# Sheet1.net
KiCad netlist of a schematic drawn in Altium Designer
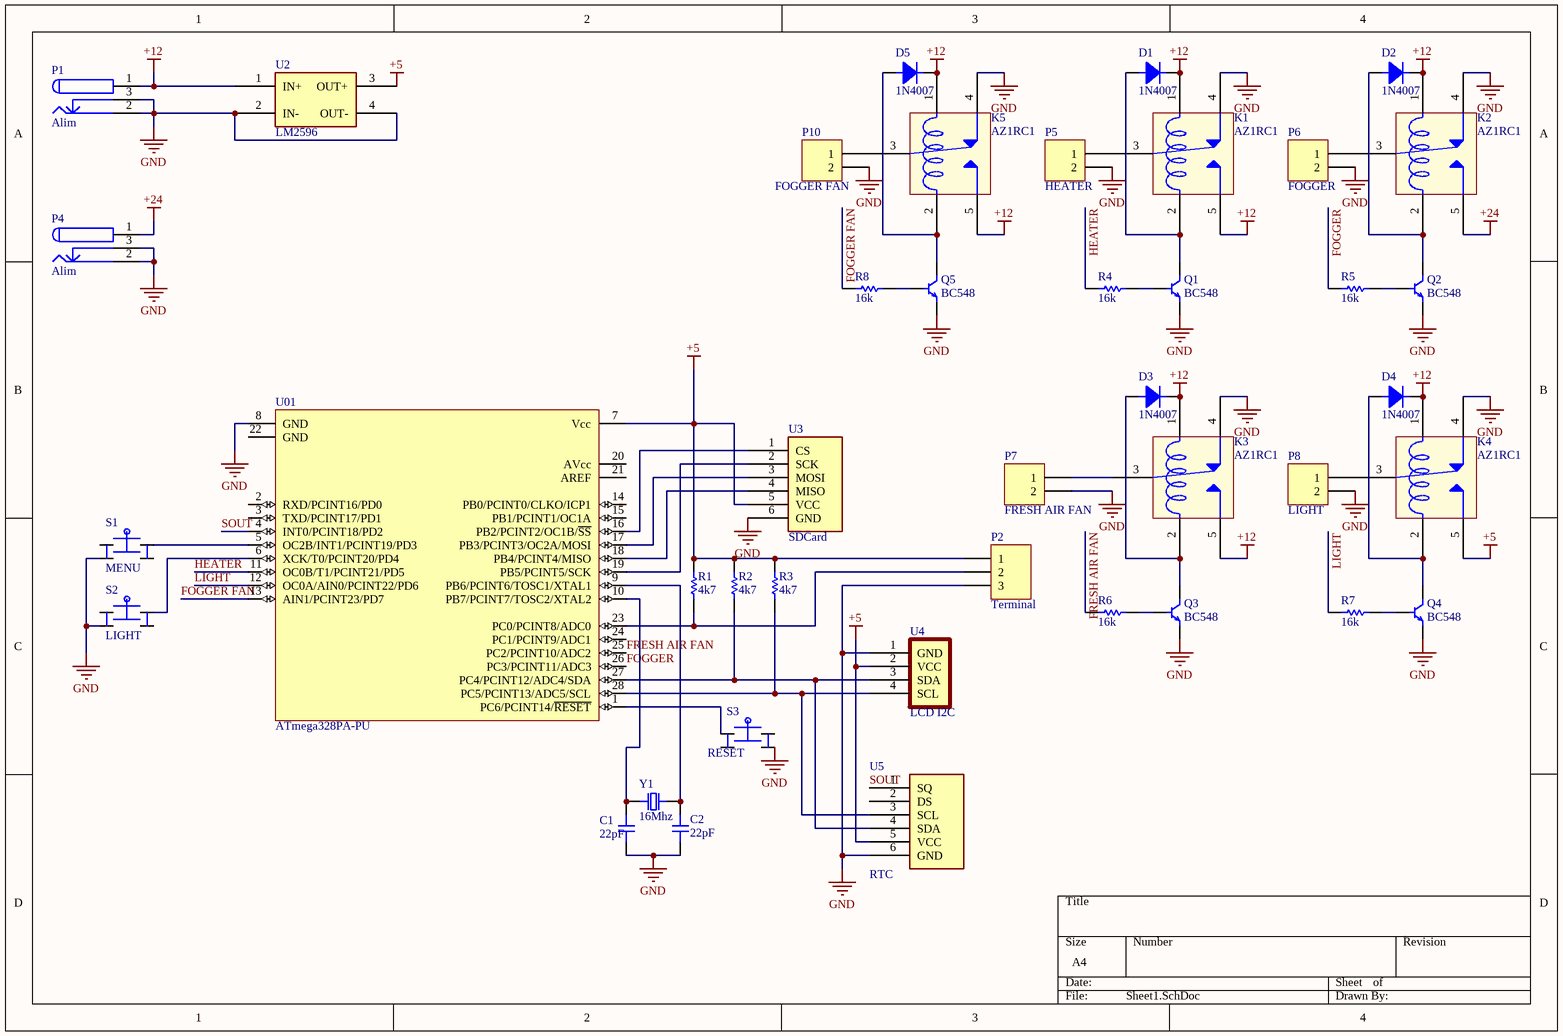
[diagram p0: Sheet1.SchDoc]

(export (version "E")
  (design (tool "Eeschema 10.0.6"))
  (components
    (comp (ref "C1")
      (value "22pF")
      (footprint "C100-200-100")
      (description "Capacitor")
      (fields (field (name "VOLTAGE") "100 V") (field (name "PUBLISHER") "Altium Limited"))
      (libsource (lib "GPDSE") (part "Capacitor"))
    )
    (comp (ref "C2")
      (value "22pF")
      (footprint "C100-200-100")
      (description "Capacitor")
      (fields (field (name "VOLTAGE") "100 V") (field (name "PUBLISHER") "Altium Limited"))
      (libsource (lib "GPDSE") (part "Capacitor"))
    )
    (comp (ref "D1")
      (value "1N4007")
      (footprint "DO-41-Plastic")
      (description "General Purpose Rectifier")
      (libsource (lib "GPDSE") (part "1N4007"))
    )
    (comp (ref "D2")
      (value "1N4007")
      (footprint "DO-41-Plastic")
      (description "General Purpose Rectifier")
      (libsource (lib "GPDSE") (part "1N4007"))
    )
    (comp (ref "D3")
      (value "1N4007")
      (footprint "DO-41-Plastic")
      (description "General Purpose Rectifier")
      (libsource (lib "GPDSE") (part "1N4007"))
    )
    (comp (ref "D4")
      (value "1N4007")
      (footprint "DO-41-Plastic")
      (description "General Purpose Rectifier")
      (libsource (lib "GPDSE") (part "1N4007"))
    )
    (comp (ref "D5")
      (value "1N4007")
      (footprint "DO-41-Plastic")
      (description "General Purpose Rectifier")
      (libsource (lib "GPDSE") (part "1N4007"))
    )
    (comp (ref "K1")
      (value "AZ1RC1")
      (footprint "Relay-A")
      (description "Miniature Relay, 10 A, 6 Vdc, 250 Vac")
      (libsource (lib "GPDSE") (part "AZ1RC1"))
    )
    (comp (ref "K2")
      (value "AZ1RC1")
      (footprint "Relay-A")
      (description "Miniature Relay, 10 A, 6 Vdc, 250 Vac")
      (libsource (lib "GPDSE") (part "AZ1RC1"))
    )
    (comp (ref "K3")
      (value "AZ1RC1")
      (footprint "Relay-A")
      (description "Miniature Relay, 10 A, 6 Vdc, 250 Vac")
      (libsource (lib "GPDSE") (part "AZ1RC1"))
    )
    (comp (ref "K4")
      (value "AZ1RC1")
      (footprint "Relay-A")
      (description "Miniature Relay, 10 A, 6 Vdc, 250 Vac")
      (libsource (lib "GPDSE") (part "AZ1RC1"))
    )
    (comp (ref "K5")
      (value "AZ1RC1")
      (footprint "Relay-A")
      (description "Miniature Relay, 10 A, 6 Vdc, 250 Vac")
      (libsource (lib "GPDSE") (part "AZ1RC1"))
    )
    (comp (ref "P1")
      (value "Alim")
      (footprint "J4-DC-005")
      (description "Jack J4")
      (libsource (lib "GPDSE") (part "Jack_J4"))
    )
    (comp (ref "P2")
      (value "Terminal")
      (footprint "KRE_3")
      (description "Terminal Block 1x3")
      (libsource (lib "GPDSE") (part "KRE_3"))
    )
    (comp (ref "P4")
      (value "Alim")
      (footprint "J4-DC-005")
      (description "Jack J4")
      (libsource (lib "GPDSE") (part "Jack_J4"))
    )
    (comp (ref "P5")
      (value "HEATER")
      (footprint "KRE_2")
      (description "Terminal Block 1x2")
      (libsource (lib "GPDSE") (part "KRE_2"))
    )
    (comp (ref "P6")
      (value "FOGGER")
      (footprint "KRE_2")
      (description "Terminal Block 1x2")
      (libsource (lib "GPDSE") (part "KRE_2"))
    )
    (comp (ref "P7")
      (value "FRESH AIR FAN")
      (footprint "KRE_2")
      (description "Terminal Block 1x2")
      (libsource (lib "GPDSE") (part "KRE_2"))
    )
    (comp (ref "P8")
      (value "LIGHT")
      (footprint "KRE_2")
      (description "Terminal Block 1x2")
      (libsource (lib "GPDSE") (part "KRE_2"))
    )
    (comp (ref "P10")
      (value "FOGGER FAN")
      (footprint "KRE_2")
      (description "Terminal Block 1x2")
      (libsource (lib "GPDSE") (part "KRE_2"))
    )
    (comp (ref "Q1")
      (value "BC548")
      (footprint "TO-92/CBE")
      (description "NPN Epitaxial Silicon Transistor")
      (fields (field (name "COMPLEMENTARY PART") "BC558"))
      (libsource (lib "GPDSE") (part "BC548"))
    )
    (comp (ref "Q2")
      (value "BC548")
      (footprint "TO-92/CBE")
      (description "NPN Epitaxial Silicon Transistor")
      (fields (field (name "COMPLEMENTARY PART") "BC558"))
      (libsource (lib "GPDSE") (part "BC548"))
    )
    (comp (ref "Q3")
      (value "BC548")
      (footprint "TO-92/CBE")
      (description "NPN Epitaxial Silicon Transistor")
      (fields (field (name "COMPLEMENTARY PART") "BC558"))
      (libsource (lib "GPDSE") (part "BC548"))
    )
    (comp (ref "Q4")
      (value "BC548")
      (footprint "TO-92/CBE")
      (description "NPN Epitaxial Silicon Transistor")
      (fields (field (name "COMPLEMENTARY PART") "BC558"))
      (libsource (lib "GPDSE") (part "BC548"))
    )
    (comp (ref "Q5")
      (value "BC548")
      (footprint "TO-92/CBE")
      (description "NPN Epitaxial Silicon Transistor")
      (fields (field (name "COMPLEMENTARY PART") "BC558"))
      (libsource (lib "GPDSE") (part "BC548"))
    )
    (comp (ref "R1")
      (value "4k7")
      (footprint "R400-2.0mm")
      (description "Resistor")
      (fields
        (field (name "TOLERANCE") "5%")
        (field (name "POWER") "1/4 W")
        (field (name "PUBLISHER") "Altium Limited")
      )
      (libsource (lib "GPDSE") (part "Resistor"))
    )
    (comp (ref "R2")
      (value "4k7")
      (footprint "R400-2.0mm")
      (description "Resistor")
      (fields
        (field (name "TOLERANCE") "5%")
        (field (name "POWER") "1/4 W")
        (field (name "PUBLISHER") "Altium Limited")
      )
      (libsource (lib "GPDSE") (part "Resistor"))
    )
    (comp (ref "R3")
      (value "4k7")
      (footprint "R400-2.0mm")
      (description "Resistor")
      (fields
        (field (name "TOLERANCE") "5%")
        (field (name "POWER") "1/4 W")
        (field (name "PUBLISHER") "Altium Limited")
      )
      (libsource (lib "GPDSE") (part "Resistor"))
    )
    (comp (ref "R4")
      (value "16k")
      (footprint "R400-2.0mm")
      (description "Resistor")
      (fields
        (field (name "TOLERANCE") "5%")
        (field (name "POWER") "1/4 W")
        (field (name "PUBLISHER") "Altium Limited")
      )
      (libsource (lib "GPDSE") (part "Resistor"))
    )
    (comp (ref "R5")
      (value "16k")
      (footprint "R400-2.0mm")
      (description "Resistor")
      (fields
        (field (name "TOLERANCE") "5%")
        (field (name "POWER") "1/4 W")
        (field (name "PUBLISHER") "Altium Limited")
      )
      (libsource (lib "GPDSE") (part "Resistor"))
    )
    (comp (ref "R6")
      (value "16k")
      (footprint "R400-2.0mm")
      (description "Resistor")
      (fields
        (field (name "TOLERANCE") "5%")
        (field (name "POWER") "1/4 W")
        (field (name "PUBLISHER") "Altium Limited")
      )
      (libsource (lib "GPDSE") (part "Resistor"))
    )
    (comp (ref "R7")
      (value "16k")
      (footprint "R400-2.0mm")
      (description "Resistor")
      (fields
        (field (name "TOLERANCE") "5%")
        (field (name "POWER") "1/4 W")
        (field (name "PUBLISHER") "Altium Limited")
      )
      (libsource (lib "GPDSE") (part "Resistor"))
    )
    (comp (ref "R8")
      (value "16k")
      (footprint "R400-2.0mm")
      (description "Resistor")
      (fields
        (field (name "TOLERANCE") "5%")
        (field (name "POWER") "1/4 W")
        (field (name "PUBLISHER") "Altium Limited")
      )
      (libsource (lib "GPDSE") (part "Resistor"))
    )
    (comp (ref "S1")
      (value "MENU")
      (footprint "DTS-6.0mm-6.0mm-THT")
      (description "Tactile Switch SPST 4 pins")
      (libsource (lib "GPDSE") (part "PushButton_4"))
    )
    (comp (ref "S2")
      (value "LIGHT")
      (footprint "DTS-6.0mm-6.0mm-THT")
      (description "Tactile Switch SPST 4 pins")
      (libsource (lib "GPDSE") (part "PushButton_4"))
    )
    (comp (ref "S3")
      (value "RESET")
      (footprint "DTS-6.0mm-6.0mm-THT")
      (description "Tactile Switch SPST 4 pins")
      (libsource (lib "GPDSE") (part "PushButton_4"))
    )
    (comp (ref "U01")
      (value "ATmega328PA-PU")
      (footprint "DIP28-300(100)")
      (description "8-bit AVR Microcontroller with 32 KB In-System Programmable Flash")
      (libsource (lib "GPDSE") (part "ATmega328PA-PU"))
    )
    (comp (ref "U2") (value "LM2596") (footprint "LM2596") (libsource (lib "Schlib1") (part "LM2596")))
    (comp (ref "U3") (value "SDCard") (footprint "SDCard") (libsource (lib "Schlib1") (part "SDCard")))
    (comp (ref "U4") (value "LCD I2C") (footprint "LCD_I2C") (libsource (lib "Schlib1") (part "LCD_I2C")))
    (comp (ref "U5") (value "RTC") (footprint "RTC") (libsource (lib "Schlib1") (part "RTC")))
    (comp (ref "Y1")
      (value "16Mhz")
      (footprint "HC49-US-THT")
      (description "Crystal")
      (libsource (lib "GPDSE") (part "Crystal"))
    )
  )
  (nets
    (net (code "1") (name "+5") (class "Default")
      (node (ref "K4") (pin "5") (pinfunction "5_5") (pintype "passive"))
      (node (ref "P2") (pin "1") (pinfunction "1_1") (pintype "passive"))
      (node (ref "R1") (pin "2") (pinfunction "2_2") (pintype "passive"))
      (node (ref "R2") (pin "2") (pinfunction "2_2") (pintype "passive"))
      (node (ref "R3") (pin "2") (pinfunction "2_2") (pintype "passive"))
      (node (ref "U01") (pin "7") (pinfunction "Vcc_7") (pintype "passive"))
      (node (ref "U2") (pin "3") (pinfunction "OUT+_3") (pintype "passive"))
      (node (ref "U3") (pin "5") (pinfunction "VCC_5") (pintype "passive"))
      (node (ref "U4") (pin "2") (pinfunction "VCC_2") (pintype "passive"))
      (node (ref "U5") (pin "5") (pinfunction "VCC_5") (pintype "passive"))
    )
    (net (code "2") (name "+12") (class "Default")
      (node (ref "D1") (pin "K") (pinfunction "K_K") (pintype "passive"))
      (node (ref "D2") (pin "K") (pinfunction "K_K") (pintype "passive"))
      (node (ref "D3") (pin "K") (pinfunction "K_K") (pintype "passive"))
      (node (ref "D4") (pin "K") (pinfunction "K_K") (pintype "passive"))
      (node (ref "D5") (pin "K") (pinfunction "K_K") (pintype "passive"))
      (node (ref "K1") (pin "1") (pinfunction "1_1") (pintype "passive"))
      (node (ref "K1") (pin "5") (pinfunction "5_5") (pintype "passive"))
      (node (ref "K2") (pin "1") (pinfunction "1_1") (pintype "passive"))
      (node (ref "K3") (pin "1") (pinfunction "1_1") (pintype "passive"))
      (node (ref "K3") (pin "5") (pinfunction "5_5") (pintype "passive"))
      (node (ref "K4") (pin "1") (pinfunction "1_1") (pintype "passive"))
      (node (ref "K5") (pin "1") (pinfunction "1_1") (pintype "passive"))
      (node (ref "K5") (pin "5") (pinfunction "5_5") (pintype "passive"))
      (node (ref "P1") (pin "1") (pinfunction "1_1") (pintype "passive"))
      (node (ref "U2") (pin "1") (pinfunction "IN+_1") (pintype "passive"))
    )
    (net (code "3") (name "+24") (class "Default")
      (node (ref "K2") (pin "5") (pinfunction "5_5") (pintype "passive"))
      (node (ref "P4") (pin "1") (pinfunction "1_1") (pintype "passive"))
    )
    (net (code "4") (name "/FOGGER") (class "Default")
      (node (ref "R5") (pin "1") (pinfunction "1_1") (pintype "passive"))
      (node (ref "U01") (pin "26") (pinfunction "PC3/PCINT11/ADC3_26") (pintype "bidirectional"))
    )
    (net (code "5") (name "/FOGGER FAN") (class "Default")
      (node (ref "R8") (pin "1") (pinfunction "1_1") (pintype "passive"))
      (node (ref "U01") (pin "13") (pinfunction "AIN1/PCINT23/PD7_13") (pintype "bidirectional"))
    )
    (net (code "6") (name "/FRESH AIR FAN") (class "Default")
      (node (ref "R6") (pin "1") (pinfunction "1_1") (pintype "passive"))
      (node (ref "U01") (pin "25") (pinfunction "PC2/PCINT10/ADC2_25") (pintype "bidirectional"))
    )
    (net (code "7") (name "/HEATER") (class "Default")
      (node (ref "R4") (pin "1") (pinfunction "1_1") (pintype "passive"))
      (node (ref "U01") (pin "11") (pinfunction "OC0B/T1/PCINT21/PD5_11") (pintype "bidirectional"))
    )
    (net (code "8") (name "/LIGHT") (class "Default")
      (node (ref "R7") (pin "1") (pinfunction "1_1") (pintype "passive"))
      (node (ref "U01") (pin "12") (pinfunction "OC0A/AIN0/PCINT22/PD6_12") (pintype "bidirectional"))
    )
    (net (code "9") (name "/SOUT") (class "Default")
      (node (ref "U01") (pin "4") (pinfunction "INT0/PCINT18/PD2_4") (pintype "bidirectional"))
      (node (ref "U5") (pin "1") (pinfunction "SQ_1") (pintype "passive"))
    )
    (net (code "10") (name "GND") (class "Default")
      (node (ref "C1") (pin "1") (pinfunction "1_1") (pintype "passive"))
      (node (ref "C2") (pin "1") (pinfunction "1_1") (pintype "passive"))
      (node (ref "K1") (pin "4") (pinfunction "4_4") (pintype "passive"))
      (node (ref "K2") (pin "4") (pinfunction "4_4") (pintype "passive"))
      (node (ref "K3") (pin "4") (pinfunction "4_4") (pintype "passive"))
      (node (ref "K4") (pin "4") (pinfunction "4_4") (pintype "passive"))
      (node (ref "K5") (pin "4") (pinfunction "4_4") (pintype "passive"))
      (node (ref "P1") (pin "2") (pinfunction "2_2") (pintype "passive"))
      (node (ref "P1") (pin "3") (pinfunction "3_3") (pintype "passive"))
      (node (ref "P10") (pin "2") (pinfunction "2_2") (pintype "passive"))
      (node (ref "P2") (pin "3") (pinfunction "3_3") (pintype "passive"))
      (node (ref "P4") (pin "2") (pinfunction "2_2") (pintype "passive"))
      (node (ref "P4") (pin "3") (pinfunction "3_3") (pintype "passive"))
      (node (ref "P5") (pin "2") (pinfunction "2_2") (pintype "passive"))
      (node (ref "P6") (pin "2") (pinfunction "2_2") (pintype "passive"))
      (node (ref "P7") (pin "2") (pinfunction "2_2") (pintype "passive"))
      (node (ref "P8") (pin "2") (pinfunction "2_2") (pintype "passive"))
      (node (ref "Q1") (pin "E") (pinfunction "E_E") (pintype "passive"))
      (node (ref "Q2") (pin "E") (pinfunction "E_E") (pintype "passive"))
      (node (ref "Q3") (pin "E") (pinfunction "E_E") (pintype "passive"))
      (node (ref "Q4") (pin "E") (pinfunction "E_E") (pintype "passive"))
      (node (ref "Q5") (pin "E") (pinfunction "E_E") (pintype "passive"))
      (node (ref "S1") (pin "2") (pinfunction "2_2") (pintype "passive"))
      (node (ref "S2") (pin "2") (pinfunction "2_2") (pintype "passive"))
      (node (ref "S3") (pin "4") (pinfunction "4_4") (pintype "passive"))
      (node (ref "U01") (pin "8") (pinfunction "GND_8") (pintype "passive"))
      (node (ref "U2") (pin "2") (pinfunction "IN-_2") (pintype "passive"))
      (node (ref "U2") (pin "4") (pinfunction "OUT-_4") (pintype "passive"))
      (node (ref "U3") (pin "6") (pinfunction "GND_6") (pintype "passive"))
      (node (ref "U4") (pin "1") (pinfunction "GND_1") (pintype "passive"))
      (node (ref "U5") (pin "6") (pinfunction "GND_6") (pintype "passive"))
    )
    (net (code "11") (name "Net-(D1-PadA)") (class "Default")
      (node (ref "D1") (pin "A") (pinfunction "A_A") (pintype "passive"))
      (node (ref "K1") (pin "2") (pinfunction "2_2") (pintype "passive"))
      (node (ref "Q1") (pin "C") (pinfunction "C_C") (pintype "passive"))
    )
    (net (code "12") (name "Net-(D2-PadA)") (class "Default")
      (node (ref "D2") (pin "A") (pinfunction "A_A") (pintype "passive"))
      (node (ref "K2") (pin "2") (pinfunction "2_2") (pintype "passive"))
      (node (ref "Q2") (pin "C") (pinfunction "C_C") (pintype "passive"))
    )
    (net (code "13") (name "Net-(D3-PadA)") (class "Default")
      (node (ref "D3") (pin "A") (pinfunction "A_A") (pintype "passive"))
      (node (ref "K3") (pin "2") (pinfunction "2_2") (pintype "passive"))
      (node (ref "Q3") (pin "C") (pinfunction "C_C") (pintype "passive"))
    )
    (net (code "14") (name "Net-(D4-PadA)") (class "Default")
      (node (ref "D4") (pin "A") (pinfunction "A_A") (pintype "passive"))
      (node (ref "K4") (pin "2") (pinfunction "2_2") (pintype "passive"))
      (node (ref "Q4") (pin "C") (pinfunction "C_C") (pintype "passive"))
    )
    (net (code "15") (name "Net-(D5-PadA)") (class "Default")
      (node (ref "D5") (pin "A") (pinfunction "A_A") (pintype "passive"))
      (node (ref "K5") (pin "2") (pinfunction "2_2") (pintype "passive"))
      (node (ref "Q5") (pin "C") (pinfunction "C_C") (pintype "passive"))
    )
    (net (code "16") (name "Net-(K1-Pad3)") (class "Default")
      (node (ref "K1") (pin "3") (pinfunction "3_3") (pintype "passive"))
      (node (ref "P5") (pin "1") (pinfunction "1_1") (pintype "passive"))
    )
    (net (code "17") (name "Net-(K2-Pad3)") (class "Default")
      (node (ref "K2") (pin "3") (pinfunction "3_3") (pintype "passive"))
      (node (ref "P6") (pin "1") (pinfunction "1_1") (pintype "passive"))
    )
    (net (code "18") (name "Net-(K3-Pad3)") (class "Default")
      (node (ref "K3") (pin "3") (pinfunction "3_3") (pintype "passive"))
      (node (ref "P7") (pin "1") (pinfunction "1_1") (pintype "passive"))
    )
    (net (code "19") (name "Net-(K4-Pad3)") (class "Default")
      (node (ref "K4") (pin "3") (pinfunction "3_3") (pintype "passive"))
      (node (ref "P8") (pin "1") (pinfunction "1_1") (pintype "passive"))
    )
    (net (code "20") (name "Net-(K5-Pad3)") (class "Default")
      (node (ref "K5") (pin "3") (pinfunction "3_3") (pintype "passive"))
      (node (ref "P10") (pin "1") (pinfunction "1_1") (pintype "passive"))
    )
    (net (code "21") (name "Net-(Q1-PadB)") (class "Default")
      (node (ref "Q1") (pin "B") (pinfunction "B_B") (pintype "passive"))
      (node (ref "R4") (pin "2") (pinfunction "2_2") (pintype "passive"))
    )
    (net (code "22") (name "Net-(Q2-PadB)") (class "Default")
      (node (ref "Q2") (pin "B") (pinfunction "B_B") (pintype "passive"))
      (node (ref "R5") (pin "2") (pinfunction "2_2") (pintype "passive"))
    )
    (net (code "23") (name "Net-(Q3-PadB)") (class "Default")
      (node (ref "Q3") (pin "B") (pinfunction "B_B") (pintype "passive"))
      (node (ref "R6") (pin "2") (pinfunction "2_2") (pintype "passive"))
    )
    (net (code "24") (name "Net-(Q4-PadB)") (class "Default")
      (node (ref "Q4") (pin "B") (pinfunction "B_B") (pintype "passive"))
      (node (ref "R7") (pin "2") (pinfunction "2_2") (pintype "passive"))
    )
    (net (code "25") (name "Net-(Q5-PadB)") (class "Default")
      (node (ref "Q5") (pin "B") (pinfunction "B_B") (pintype "passive"))
      (node (ref "R8") (pin "2") (pinfunction "2_2") (pintype "passive"))
    )
    (net (code "26") (name "Net-(U01-OC2B{slash}INT1{slash}PCINT19{slash}PD3)") (class "Default")
      (node (ref "S1") (pin "3") (pinfunction "3_3") (pintype "passive"))
      (node (ref "U01") (pin "5") (pinfunction "OC2B/INT1/PCINT19/PD3_5") (pintype "bidirectional"))
    )
    (net (code "27") (name "Net-(U01-PB2{slash}PCINT2{slash}OC1B{slash}~{SS})") (class "Default")
      (node (ref "U01") (pin "16") (pinfunction "PB2/PCINT2/OC1B/~{SS}_16") (pintype "bidirectional"))
      (node (ref "U3") (pin "1") (pinfunction "CS_1") (pintype "passive"))
    )
    (net (code "28") (name "Net-(U01-PB3{slash}PCINT3{slash}OC2A{slash}MOSI)") (class "Default")
      (node (ref "U01") (pin "17") (pinfunction "PB3/PCINT3/OC2A/MOSI_17") (pintype "bidirectional"))
      (node (ref "U3") (pin "3") (pinfunction "MOSI_3") (pintype "passive"))
    )
    (net (code "29") (name "Net-(U01-PB4{slash}PCINT4{slash}MISO)") (class "Default")
      (node (ref "U01") (pin "18") (pinfunction "PB4/PCINT4/MISO_18") (pintype "bidirectional"))
      (node (ref "U3") (pin "4") (pinfunction "MISO_4") (pintype "passive"))
    )
    (net (code "30") (name "Net-(U01-PB5{slash}PCINT5{slash}SCK)") (class "Default")
      (node (ref "U01") (pin "19") (pinfunction "PB5/PCINT5/SCK_19") (pintype "bidirectional"))
      (node (ref "U3") (pin "2") (pinfunction "SCK_2") (pintype "passive"))
    )
    (net (code "31") (name "Net-(U01-PB6{slash}PCINT6{slash}TOSC1{slash}XTAL1)") (class "Default")
      (node (ref "C2") (pin "2") (pinfunction "2_2") (pintype "passive"))
      (node (ref "U01") (pin "9") (pinfunction "PB6/PCINT6/TOSC1/XTAL1_9") (pintype "bidirectional"))
      (node (ref "Y1") (pin "1") (pinfunction "1_1") (pintype "passive"))
    )
    (net (code "32") (name "Net-(U01-PB7{slash}PCINT7{slash}TOSC2{slash}XTAL2)") (class "Default")
      (node (ref "C1") (pin "2") (pinfunction "2_2") (pintype "passive"))
      (node (ref "U01") (pin "10") (pinfunction "PB7/PCINT7/TOSC2/XTAL2_10") (pintype "bidirectional"))
      (node (ref "Y1") (pin "2") (pinfunction "2_2") (pintype "passive"))
    )
    (net (code "33") (name "Net-(U01-PC0{slash}PCINT8{slash}ADC0)") (class "Default")
      (node (ref "P2") (pin "2") (pinfunction "2_2") (pintype "passive"))
      (node (ref "R1") (pin "1") (pinfunction "1_1") (pintype "passive"))
      (node (ref "U01") (pin "23") (pinfunction "PC0/PCINT8/ADC0_23") (pintype "bidirectional"))
    )
    (net (code "34") (name "Net-(U01-PC4{slash}PCINT12{slash}ADC4{slash}SDA)") (class "Default")
      (node (ref "R2") (pin "1") (pinfunction "1_1") (pintype "passive"))
      (node (ref "U01") (pin "27") (pinfunction "PC4/PCINT12/ADC4/SDA_27") (pintype "bidirectional"))
      (node (ref "U4") (pin "3") (pinfunction "SDA_3") (pintype "passive"))
      (node (ref "U5") (pin "4") (pinfunction "SDA_4") (pintype "passive"))
    )
    (net (code "35") (name "Net-(U01-PC5{slash}PCINT13{slash}ADC5{slash}SCL)") (class "Default")
      (node (ref "R3") (pin "1") (pinfunction "1_1") (pintype "passive"))
      (node (ref "U01") (pin "28") (pinfunction "PC5/PCINT13/ADC5/SCL_28") (pintype "bidirectional"))
      (node (ref "U4") (pin "4") (pinfunction "SCL_4") (pintype "passive"))
      (node (ref "U5") (pin "3") (pinfunction "SCL_3") (pintype "passive"))
    )
    (net (code "36") (name "Net-(U01-PC6{slash}PCINT14{slash}~{RESET})") (class "Default")
      (node (ref "S3") (pin "1") (pinfunction "1_1") (pintype "passive"))
      (node (ref "U01") (pin "1") (pinfunction "PC6/PCINT14/~{RESET}_1") (pintype "bidirectional"))
    )
    (net (code "37") (name "Net-(U01-XCK{slash}T0{slash}PCINT20{slash}PD4)") (class "Default")
      (node (ref "S2") (pin "3") (pinfunction "3_3") (pintype "passive"))
      (node (ref "U01") (pin "6") (pinfunction "XCK/T0/PCINT20/PD4_6") (pintype "bidirectional"))
    )
    (net (code "38") (name "unconnected-(S1-Pad1)") (class "Default")
      (node (ref "S1") (pin "1") (pinfunction "1_1") (pintype "passive"))
    )
    (net (code "39") (name "unconnected-(S1-Pad4)") (class "Default")
      (node (ref "S1") (pin "4") (pinfunction "4_4") (pintype "passive"))
    )
    (net (code "40") (name "unconnected-(S2-Pad1)") (class "Default")
      (node (ref "S2") (pin "1") (pinfunction "1_1") (pintype "passive"))
    )
    (net (code "41") (name "unconnected-(S2-Pad4)") (class "Default")
      (node (ref "S2") (pin "4") (pinfunction "4_4") (pintype "passive"))
    )
    (net (code "42") (name "unconnected-(S3-Pad2)") (class "Default")
      (node (ref "S3") (pin "2") (pinfunction "2_2") (pintype "passive"))
    )
    (net (code "43") (name "unconnected-(S3-Pad3)") (class "Default")
      (node (ref "S3") (pin "3") (pinfunction "3_3") (pintype "passive"))
    )
    (net (code "44") (name "unconnected-(U01-AREF-Pad21)") (class "Default")
      (node (ref "U01") (pin "21") (pinfunction "AREF_21") (pintype "passive"))
    )
    (net (code "45") (name "unconnected-(U01-AVcc-Pad20)") (class "Default")
      (node (ref "U01") (pin "20") (pinfunction "AVcc_20") (pintype "passive"))
    )
    (net (code "46") (name "unconnected-(U01-GND-Pad22)") (class "Default")
      (node (ref "U01") (pin "22") (pinfunction "GND_22") (pintype "passive"))
    )
    (net (code "47") (name "unconnected-(U01-PB0{slash}PCINT0{slash}CLKO{slash}ICP1-Pad14)") (class "Default")
      (node (ref "U01") (pin "14") (pinfunction "PB0/PCINT0/CLKO/ICP1_14") (pintype "bidirectional"))
    )
    (net (code "48") (name "unconnected-(U01-PB1{slash}PCINT1{slash}OC1A-Pad15)") (class "Default")
      (node (ref "U01") (pin "15") (pinfunction "PB1/PCINT1/OC1A_15") (pintype "bidirectional"))
    )
    (net (code "49") (name "unconnected-(U01-PC1{slash}PCINT9{slash}ADC1-Pad24)") (class "Default")
      (node (ref "U01") (pin "24") (pinfunction "PC1/PCINT9/ADC1_24") (pintype "bidirectional"))
    )
    (net (code "50") (name "unconnected-(U01-RXD{slash}PCINT16{slash}PD0-Pad2)") (class "Default")
      (node (ref "U01") (pin "2") (pinfunction "RXD/PCINT16/PD0_2") (pintype "bidirectional"))
    )
    (net (code "51") (name "unconnected-(U01-TXD{slash}PCINT17{slash}PD1-Pad3)") (class "Default")
      (node (ref "U01") (pin "3") (pinfunction "TXD/PCINT17/PD1_3") (pintype "bidirectional"))
    )
    (net (code "52") (name "unconnected-(U5-DS-Pad2)") (class "Default")
      (node (ref "U5") (pin "2") (pinfunction "DS_2") (pintype "passive"))
    )
  )
)
